# ADS1115-Breakout-5V.net
KiCad netlist of a schematic drawn in EAGLE
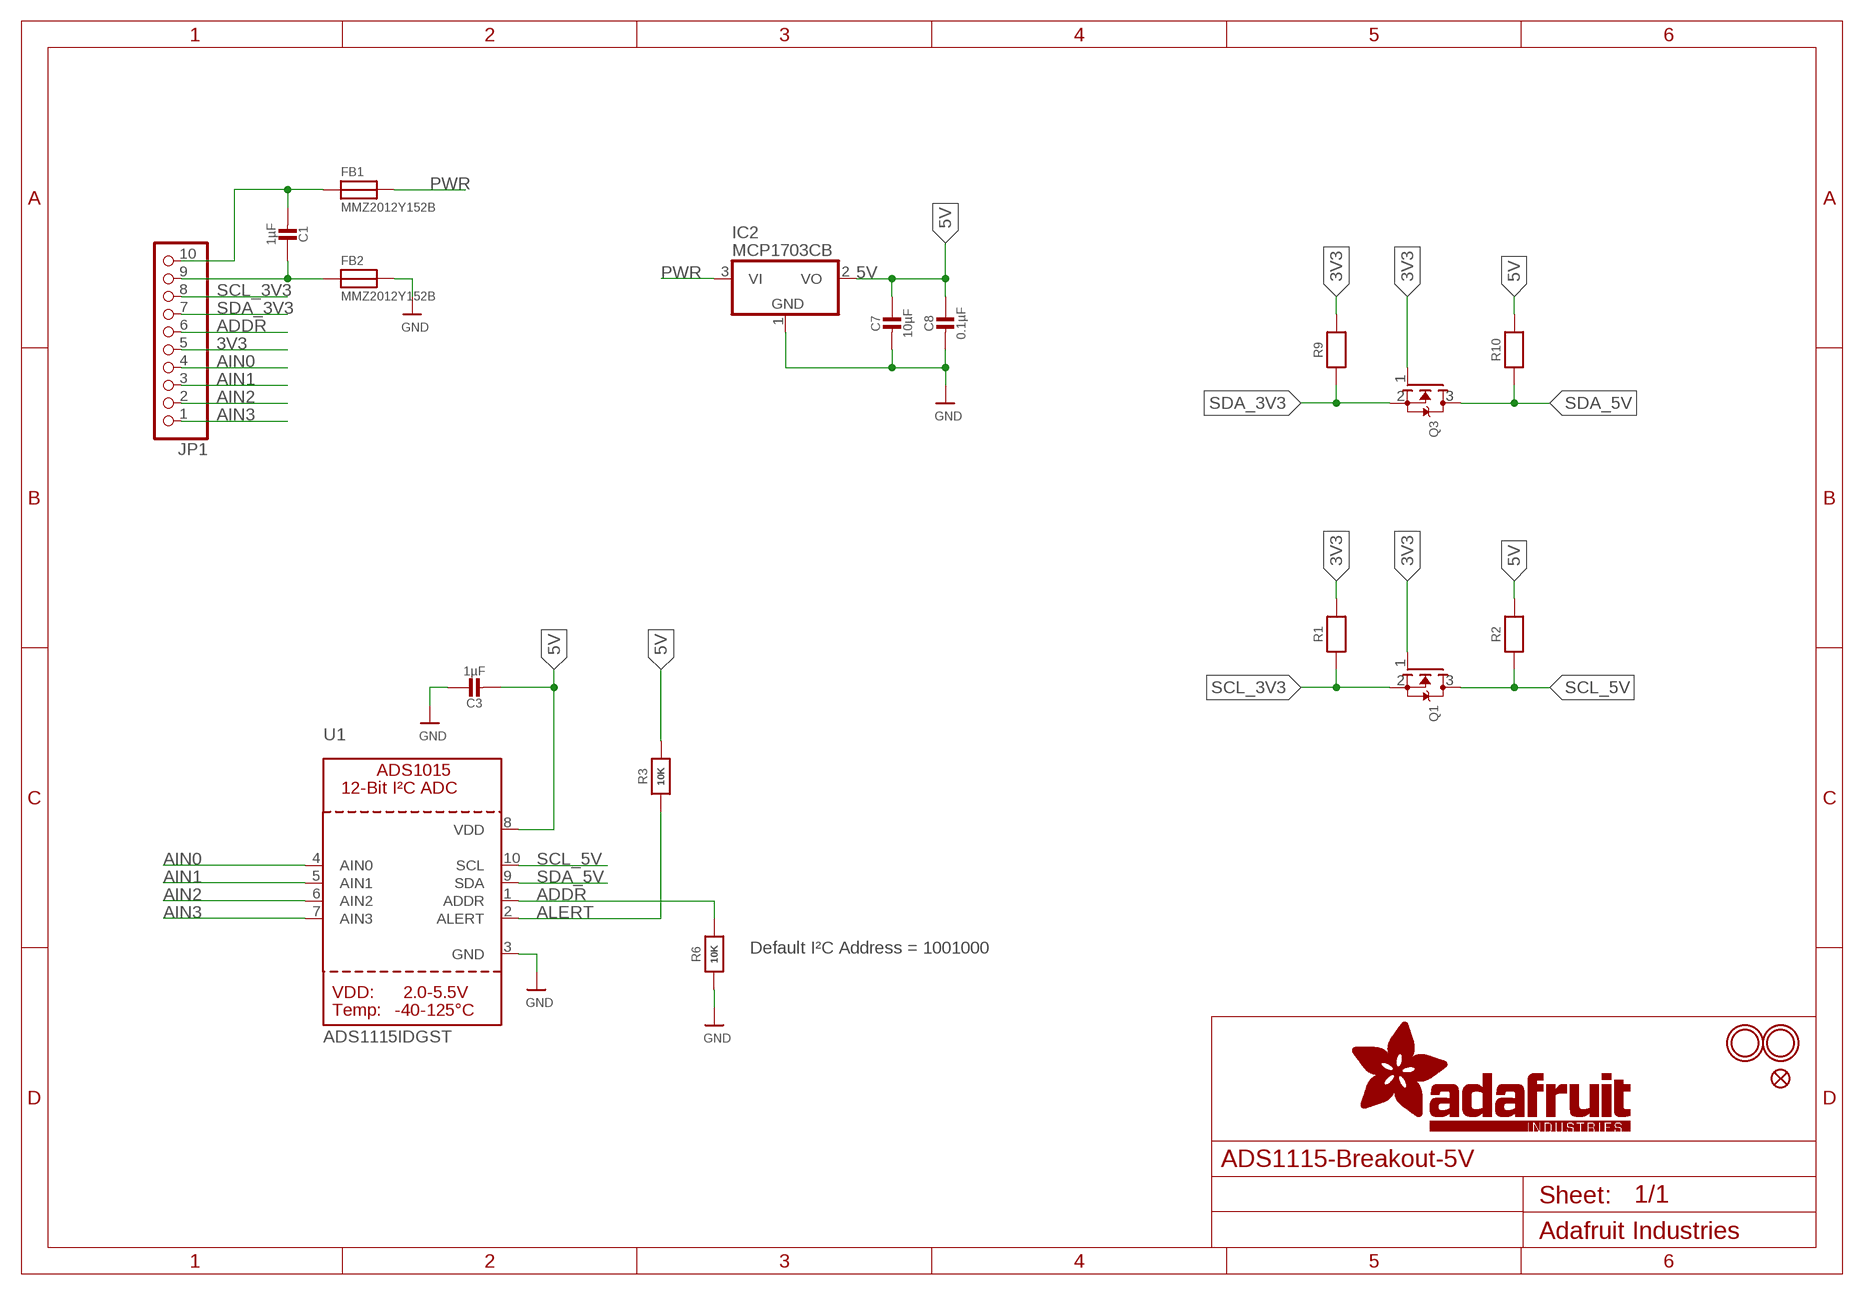
[diagram p0: schematic, sheet 1]

(export (version "E")
  (design (tool "Eeschema 10.0.6"))
  (components
    (comp (ref "C1")
      (value "1µF")
      (footprint "eagle-import:_0402MP")
      (libsource (lib "eagle-import") (part "CAP_CERAMIC_0402MP"))
    )
    (comp (ref "C3")
      (value "1µF")
      (footprint "eagle-import:_0402MP")
      (libsource (lib "eagle-import") (part "CAP_CERAMIC_0402MP"))
    )
    (comp (ref "C7")
      (value "10µF")
      (footprint "eagle-import:_0402MP")
      (libsource (lib "eagle-import") (part "CAP_CERAMIC_0402MP"))
    )
    (comp (ref "C8")
      (value "0.1µF")
      (footprint "eagle-import:_0402MP")
      (libsource (lib "eagle-import") (part "CAP_CERAMIC_0402MP"))
    )
    (comp (ref "FB1")
      (value "MMZ2012Y152B")
      (footprint "eagle-import:0805")
      (libsource (lib "eagle-import") (part "FERRITE0805"))
    )
    (comp (ref "FB2")
      (value "MMZ2012Y152B")
      (footprint "eagle-import:0805")
      (libsource (lib "eagle-import") (part "FERRITE0805"))
    )
    (comp (ref "FID1")
      (value "FIDUCIAL\"\"")
      (footprint "eagle-import:FIDUCIAL_1MM")
      (libsource (lib "eagle-import") (part "FIDUCIAL{dblquote}{dblquote}"))
    )
    (comp (ref "IC2")
      (value "MCP1703CB")
      (footprint "eagle-import:SOT23")
      (libsource (lib "eagle-import") (part "MCP1703CB"))
    )
    (comp (ref "JP1")
      (value "HEADER-1X1070MIL")
      (footprint "eagle-import:1X10_ROUND70")
      (libsource (lib "eagle-import") (part "HEADER-1X1070MIL"))
    )
    (comp (ref "Q1")
      (value "MOSFET-NREFLOW")
      (footprint "eagle-import:SOT23")
      (libsource (lib "eagle-import") (part "MOSFET-NREFLOW"))
    )
    (comp (ref "Q3")
      (value "MOSFET-NREFLOW")
      (footprint "eagle-import:SOT23")
      (libsource (lib "eagle-import") (part "MOSFET-NREFLOW"))
    )
    (comp (ref "R1")
      (value "RESISTOR_0402MP")
      (footprint "eagle-import:_0402MP")
      (libsource (lib "eagle-import") (part "RESISTOR_0402MP"))
    )
    (comp (ref "R2")
      (value "RESISTOR_0402MP")
      (footprint "eagle-import:_0402MP")
      (libsource (lib "eagle-import") (part "RESISTOR_0402MP"))
    )
    (comp (ref "R3")
      (value "10K")
      (footprint "eagle-import:_0402MP")
      (libsource (lib "eagle-import") (part "RESISTOR_0402MP"))
    )
    (comp (ref "R6")
      (value "10K")
      (footprint "eagle-import:_0402MP")
      (libsource (lib "eagle-import") (part "RESISTOR_0402MP"))
    )
    (comp (ref "R9")
      (value "RESISTOR_0402MP")
      (footprint "eagle-import:_0402MP")
      (libsource (lib "eagle-import") (part "RESISTOR_0402MP"))
    )
    (comp (ref "R10")
      (value "RESISTOR_0402MP")
      (footprint "eagle-import:_0402MP")
      (libsource (lib "eagle-import") (part "RESISTOR_0402MP"))
    )
    (comp (ref "U$13")
      (value "MOUNTINGHOLE2.5")
      (footprint "eagle-import:MOUNTINGHOLE_2.5_PLATED")
      (libsource (lib "eagle-import") (part "MOUNTINGHOLE2.5"))
    )
    (comp (ref "U$14")
      (value "MOUNTINGHOLE2.5")
      (footprint "eagle-import:MOUNTINGHOLE_2.5_PLATED")
      (libsource (lib "eagle-import") (part "MOUNTINGHOLE2.5"))
    )
    (comp (ref "U1")
      (value "ADS1115IDGST")
      (footprint "eagle-import:MSOP10")
      (libsource (lib "eagle-import") (part "ADC_ADS1015"))
    )
  )
  (nets
    (net (code "1") (name "/ADDR") (class "Default")
      (node (ref "JP1") (pin "6") (pinfunction "6_6") (pintype "passive"))
      (node (ref "R6") (pin "2") (pinfunction "2_2") (pintype "passive"))
      (node (ref "U1") (pin "1") (pinfunction "ADDR_1") (pintype "bidirectional"))
    )
    (net (code "2") (name "/AIN0") (class "Default")
      (node (ref "JP1") (pin "4") (pinfunction "4_4") (pintype "passive"))
      (node (ref "U1") (pin "4") (pinfunction "AIN0_4") (pintype "bidirectional"))
    )
    (net (code "3") (name "/AIN1") (class "Default")
      (node (ref "JP1") (pin "3") (pinfunction "3_3") (pintype "passive"))
      (node (ref "U1") (pin "5") (pinfunction "AIN1_5") (pintype "bidirectional"))
    )
    (net (code "4") (name "/AIN2") (class "Default")
      (node (ref "JP1") (pin "2") (pinfunction "2_2") (pintype "passive"))
      (node (ref "U1") (pin "6") (pinfunction "AIN2_6") (pintype "bidirectional"))
    )
    (net (code "5") (name "/AIN3") (class "Default")
      (node (ref "JP1") (pin "1") (pinfunction "1_1") (pintype "passive"))
      (node (ref "U1") (pin "7") (pinfunction "AIN3_7") (pintype "bidirectional"))
    )
    (net (code "6") (name "/ALERT") (class "Default")
      (node (ref "R3") (pin "1") (pinfunction "1_1") (pintype "passive"))
      (node (ref "U1") (pin "2") (pinfunction "ALERT_2") (pintype "bidirectional"))
    )
    (net (code "7") (name "/PWR") (class "Default")
      (node (ref "FB1") (pin "2") (pinfunction "P$2_2") (pintype "bidirectional"))
      (node (ref "IC2") (pin "3") (pinfunction "VI_3") (pintype "input"))
    )
    (net (code "8") (name "3V3") (class "Default")
      (node (ref "JP1") (pin "5") (pinfunction "5_5") (pintype "passive"))
      (node (ref "Q1") (pin "1") (pinfunction "G_1") (pintype "bidirectional"))
      (node (ref "Q3") (pin "1") (pinfunction "G_1") (pintype "bidirectional"))
      (node (ref "R1") (pin "2") (pinfunction "2_2") (pintype "passive"))
      (node (ref "R9") (pin "2") (pinfunction "2_2") (pintype "passive"))
    )
    (net (code "9") (name "5V") (class "Default")
      (node (ref "C3") (pin "2") (pinfunction "2_2") (pintype "passive"))
      (node (ref "C7") (pin "1") (pinfunction "1_1") (pintype "passive"))
      (node (ref "C8") (pin "1") (pinfunction "1_1") (pintype "passive"))
      (node (ref "IC2") (pin "2") (pinfunction "VO_2") (pintype "passive"))
      (node (ref "R10") (pin "2") (pinfunction "2_2") (pintype "passive"))
      (node (ref "R2") (pin "2") (pinfunction "2_2") (pintype "passive"))
      (node (ref "R3") (pin "2") (pinfunction "2_2") (pintype "passive"))
      (node (ref "U1") (pin "8") (pinfunction "VDD_8") (pintype "bidirectional"))
    )
    (net (code "10") (name "GND") (class "Default")
      (node (ref "C3") (pin "1") (pinfunction "1_1") (pintype "passive"))
      (node (ref "C7") (pin "2") (pinfunction "2_2") (pintype "passive"))
      (node (ref "C8") (pin "2") (pinfunction "2_2") (pintype "passive"))
      (node (ref "FB2") (pin "2") (pinfunction "P$2_2") (pintype "bidirectional"))
      (node (ref "IC2") (pin "1") (pinfunction "GND_1") (pintype "passive"))
      (node (ref "R6") (pin "1") (pinfunction "1_1") (pintype "passive"))
      (node (ref "U1") (pin "3") (pinfunction "GND_3") (pintype "bidirectional"))
    )
    (net (code "11") (name "Net-(FB1-P$1)") (class "Default")
      (node (ref "C1") (pin "2") (pinfunction "2_2") (pintype "passive"))
      (node (ref "FB1") (pin "1") (pinfunction "P$1_1") (pintype "bidirectional"))
      (node (ref "JP1") (pin "10") (pinfunction "10_10") (pintype "passive"))
    )
    (net (code "12") (name "Net-(FB2-P$1)") (class "Default")
      (node (ref "C1") (pin "1") (pinfunction "1_1") (pintype "passive"))
      (node (ref "FB2") (pin "1") (pinfunction "P$1_1") (pintype "bidirectional"))
      (node (ref "JP1") (pin "9") (pinfunction "9_9") (pintype "passive"))
    )
    (net (code "13") (name "SCL_3V3") (class "Default")
      (node (ref "JP1") (pin "8") (pinfunction "8_8") (pintype "passive"))
      (node (ref "Q1") (pin "2") (pinfunction "S_2") (pintype "bidirectional"))
      (node (ref "R1") (pin "1") (pinfunction "1_1") (pintype "passive"))
    )
    (net (code "14") (name "SCL_5V") (class "Default")
      (node (ref "Q1") (pin "3") (pinfunction "D_3") (pintype "bidirectional"))
      (node (ref "R2") (pin "1") (pinfunction "1_1") (pintype "passive"))
      (node (ref "U1") (pin "10") (pinfunction "SCL_10") (pintype "bidirectional"))
    )
    (net (code "15") (name "SDA_3V3") (class "Default")
      (node (ref "JP1") (pin "7") (pinfunction "7_7") (pintype "passive"))
      (node (ref "Q3") (pin "2") (pinfunction "S_2") (pintype "bidirectional"))
      (node (ref "R9") (pin "1") (pinfunction "1_1") (pintype "passive"))
    )
    (net (code "16") (name "SDA_5V") (class "Default")
      (node (ref "Q3") (pin "3") (pinfunction "D_3") (pintype "bidirectional"))
      (node (ref "R10") (pin "1") (pinfunction "1_1") (pintype "passive"))
      (node (ref "U1") (pin "9") (pinfunction "SDA_9") (pintype "bidirectional"))
    )
  )
)
